# SSLidarboard.net
KiCad netlist of a schematic drawn in EAGLE
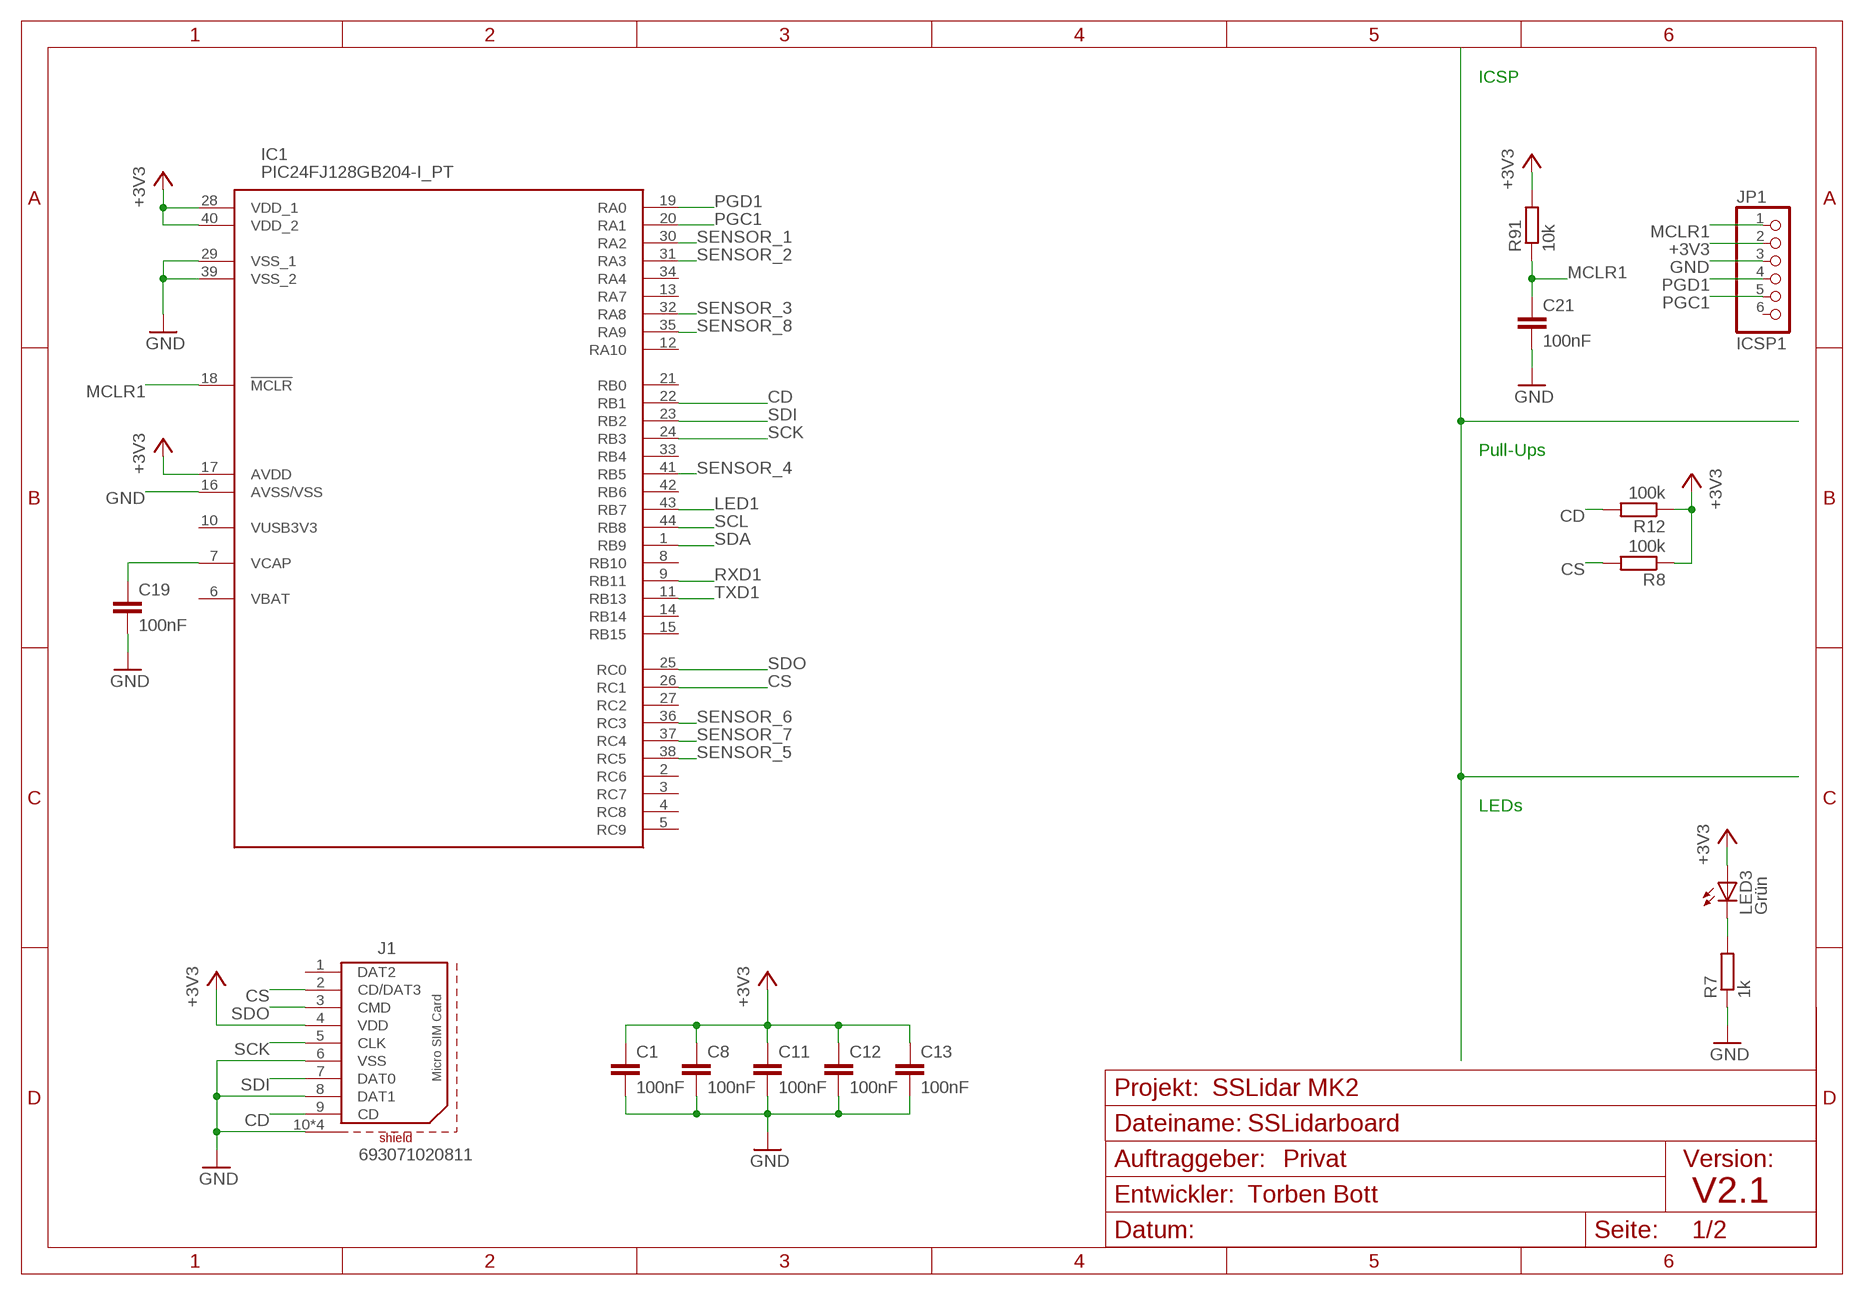
[diagram p0: schematic, sheet 1]
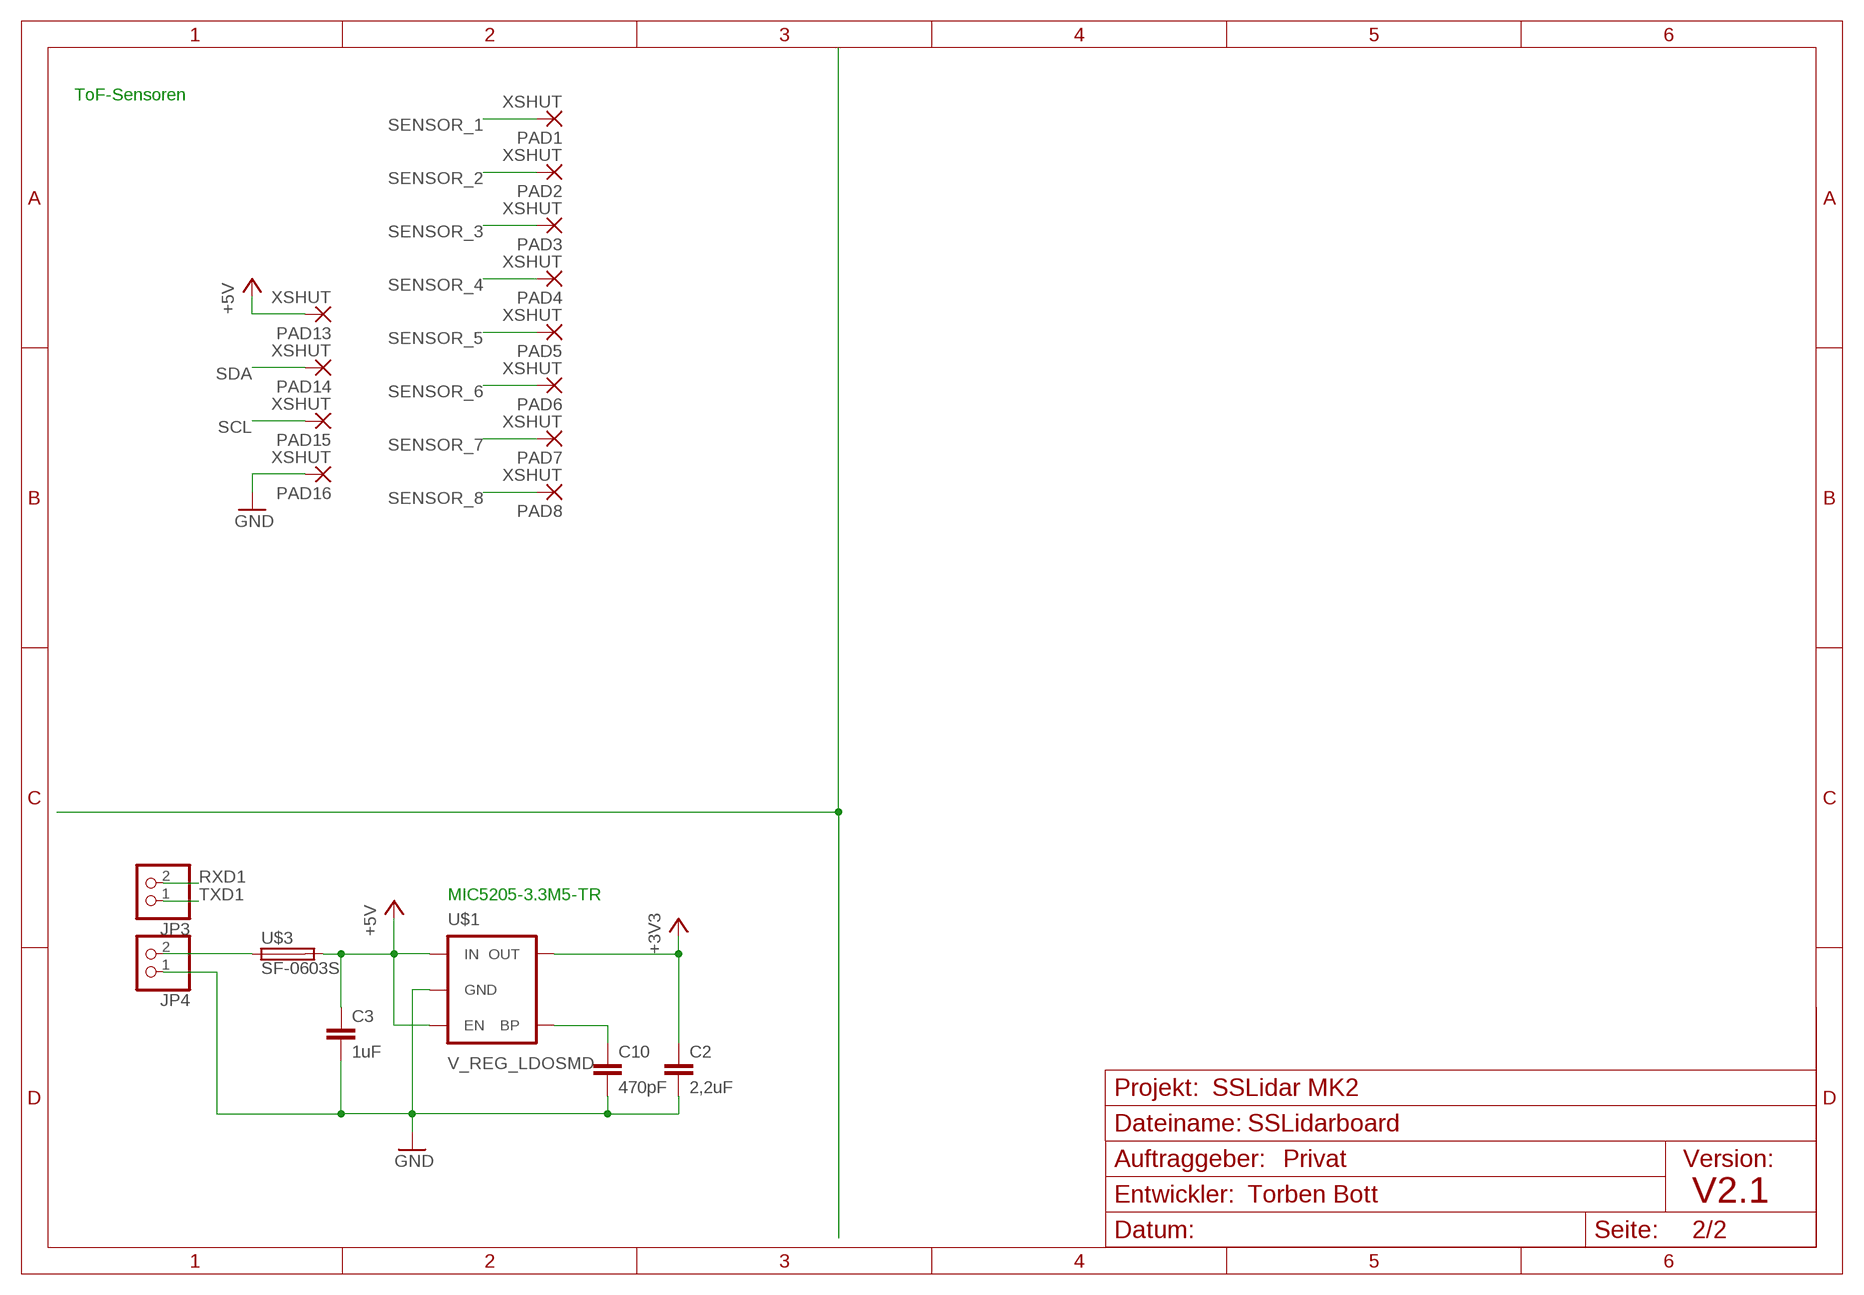
[diagram p1: schematic, sheet 2]

(export (version "E")
  (design (tool "Eeschema 10.0.6"))
  (components
    (comp (ref "C1")
      (value "100nF")
      (footprint "eagle-import:C0805")
      (libsource (lib "eagle-import") (part "C-EUC0805"))
    )
    (comp (ref "C8")
      (value "100nF")
      (footprint "eagle-import:C0805")
      (libsource (lib "eagle-import") (part "C-EUC0805"))
    )
    (comp (ref "C11")
      (value "100nF")
      (footprint "eagle-import:C0805")
      (libsource (lib "eagle-import") (part "C-EUC0805"))
    )
    (comp (ref "C12")
      (value "100nF")
      (footprint "eagle-import:C0805")
      (libsource (lib "eagle-import") (part "C-EUC0805"))
    )
    (comp (ref "C13")
      (value "100nF")
      (footprint "eagle-import:C0805")
      (libsource (lib "eagle-import") (part "C-EUC0805"))
    )
    (comp (ref "C19")
      (value "100nF")
      (footprint "eagle-import:C0805")
      (libsource (lib "eagle-import") (part "C-EUC0805"))
    )
    (comp (ref "C21")
      (value "100nF")
      (footprint "eagle-import:C0805")
      (libsource (lib "eagle-import") (part "C-EUC0805"))
    )
    (comp (ref "IC1")
      (value "PIC24FJ128GB204-I_PT")
      (footprint "eagle-import:QFP80P1200X1200X120-44N")
      (fields
        (field (name "MANUFACTURER_PART_NUMBER") "PIC24FJ128GB204-I/PT")
        (field (name "MOUSER_PART_NUMBER") "579-P24FJ128GB204IPT")
      )
      (libsource (lib "eagle-import") (part "PIC24FJ128GB204-I_PT"))
    )
    (comp (ref "J1")
      (value "693071020811")
      (footprint "eagle-import:693071020811")
      (libsource (lib "eagle-import") (part "693071020811"))
    )
    (comp (ref "JP1")
      (value "ICSP1")
      (footprint "eagle-import:1X06")
      (libsource (lib "eagle-import") (part "PINHD-1X6"))
    )
    (comp (ref "LED3")
      (value "Grün")
      (footprint "eagle-import:CHIPLED_0805")
      (libsource (lib "eagle-import") (part "LEDCHIPLED_0805"))
    )
    (comp (ref "R7")
      (value "1k")
      (footprint "eagle-import:R0805")
      (libsource (lib "eagle-import") (part "R-EU_R0805"))
    )
    (comp (ref "R8")
      (value "100k")
      (footprint "eagle-import:R0805")
      (libsource (lib "eagle-import") (part "R-EU_R0805"))
    )
    (comp (ref "R12")
      (value "100k")
      (footprint "eagle-import:R0805")
      (libsource (lib "eagle-import") (part "R-EU_R0805"))
    )
    (comp (ref "R91")
      (value "10k")
      (footprint "eagle-import:R0805")
      (libsource (lib "eagle-import") (part "R-EU_R0805"))
    )
    (comp (ref "C2")
      (value "2,2uF")
      (footprint "eagle-import:C0805")
      (libsource (lib "eagle-import") (part "C-EUC0805"))
    )
    (comp (ref "C3")
      (value "1uF")
      (footprint "eagle-import:C0805")
      (libsource (lib "eagle-import") (part "C-EUC0805"))
    )
    (comp (ref "C10")
      (value "470pF")
      (footprint "eagle-import:C0805")
      (libsource (lib "eagle-import") (part "C-EUC0805"))
    )
    (comp (ref "JP3")
      (value "PINHD-1X2")
      (footprint "eagle-import:1X02")
      (libsource (lib "eagle-import") (part "PINHD-1X2"))
    )
    (comp (ref "JP4")
      (value "PINHD-1X2")
      (footprint "eagle-import:1X02")
      (libsource (lib "eagle-import") (part "PINHD-1X2"))
    )
    (comp (ref "PAD1")
      (value "XSHUT")
      (footprint "eagle-import:SMD1,27-2,54")
      (libsource (lib "eagle-import") (part "WIREPADSMD1,27-254"))
    )
    (comp (ref "PAD2")
      (value "XSHUT")
      (footprint "eagle-import:SMD1,27-2,54")
      (libsource (lib "eagle-import") (part "WIREPADSMD1,27-254"))
    )
    (comp (ref "PAD3")
      (value "XSHUT")
      (footprint "eagle-import:SMD1,27-2,54")
      (libsource (lib "eagle-import") (part "WIREPADSMD1,27-254"))
    )
    (comp (ref "PAD4")
      (value "XSHUT")
      (footprint "eagle-import:SMD1,27-2,54")
      (libsource (lib "eagle-import") (part "WIREPADSMD1,27-254"))
    )
    (comp (ref "PAD5")
      (value "XSHUT")
      (footprint "eagle-import:SMD1,27-2,54")
      (libsource (lib "eagle-import") (part "WIREPADSMD1,27-254"))
    )
    (comp (ref "PAD6")
      (value "XSHUT")
      (footprint "eagle-import:SMD1,27-2,54")
      (libsource (lib "eagle-import") (part "WIREPADSMD1,27-254"))
    )
    (comp (ref "PAD7")
      (value "XSHUT")
      (footprint "eagle-import:SMD1,27-2,54")
      (libsource (lib "eagle-import") (part "WIREPADSMD1,27-254"))
    )
    (comp (ref "PAD8")
      (value "XSHUT")
      (footprint "eagle-import:SMD1,27-2,54")
      (libsource (lib "eagle-import") (part "WIREPADSMD1,27-254"))
    )
    (comp (ref "PAD13")
      (value "XSHUT")
      (footprint "eagle-import:SMD1,27-2,54")
      (libsource (lib "eagle-import") (part "WIREPADSMD1,27-254"))
    )
    (comp (ref "PAD14")
      (value "XSHUT")
      (footprint "eagle-import:SMD1,27-2,54")
      (libsource (lib "eagle-import") (part "WIREPADSMD1,27-254"))
    )
    (comp (ref "PAD15")
      (value "XSHUT")
      (footprint "eagle-import:SMD1,27-2,54")
      (libsource (lib "eagle-import") (part "WIREPADSMD1,27-254"))
    )
    (comp (ref "PAD16")
      (value "XSHUT")
      (footprint "eagle-import:SMD1,27-2,54")
      (libsource (lib "eagle-import") (part "WIREPADSMD1,27-254"))
    )
    (comp (ref "U$1")
      (value "V_REG_LDOSMD")
      (footprint "eagle-import:SOT23-5")
      (libsource (lib "eagle-import") (part "V_REG_LDOSMD"))
    )
    (comp (ref "U$3")
      (value "SF-0603S")
      (footprint "eagle-import:R0603")
      (libsource (lib "eagle-import") (part "SF-0603S"))
    )
  )
  (nets
    (net (code "1") (name "+3V3") (class "Default")
      (node (ref "C1") (pin "1") (pinfunction "1_1") (pintype "passive"))
      (node (ref "C11") (pin "1") (pinfunction "1_1") (pintype "passive"))
      (node (ref "C12") (pin "1") (pinfunction "1_1") (pintype "passive"))
      (node (ref "C13") (pin "1") (pinfunction "1_1") (pintype "passive"))
      (node (ref "C2") (pin "1") (pinfunction "1_1") (pintype "passive"))
      (node (ref "C8") (pin "1") (pinfunction "1_1") (pintype "passive"))
      (node (ref "IC1") (pin "17") (pinfunction "AVDD_17") (pintype "power_in"))
      (node (ref "IC1") (pin "28") (pinfunction "VDD_1_28") (pintype "power_in"))
      (node (ref "IC1") (pin "40") (pinfunction "VDD_2_40") (pintype "power_in"))
      (node (ref "J1") (pin "4") (pinfunction "VDD_4") (pintype "bidirectional"))
      (node (ref "JP1") (pin "2") (pinfunction "2_2") (pintype "passive"))
      (node (ref "LED3") (pin "A") (pinfunction "A_A") (pintype "passive"))
      (node (ref "R12") (pin "1") (pinfunction "1_1") (pintype "passive"))
      (node (ref "R8") (pin "1") (pinfunction "1_1") (pintype "passive"))
      (node (ref "R91") (pin "2") (pinfunction "2_2") (pintype "passive"))
      (node (ref "U$1") (pin "5") (pinfunction "OUT_5") (pintype "passive"))
    )
    (net (code "2") (name "+5V") (class "Default")
      (node (ref "C3") (pin "1") (pinfunction "1_1") (pintype "passive"))
      (node (ref "PAD13") (pin "1") (pinfunction "P_1") (pintype "passive"))
      (node (ref "U$1") (pin "1") (pinfunction "IN_1") (pintype "input"))
      (node (ref "U$1") (pin "3") (pinfunction "EN_3") (pintype "input"))
      (node (ref "U$3") (pin "2") (pinfunction "2_2") (pintype "passive"))
    )
    (net (code "3") (name "CD") (class "Default")
      (node (ref "IC1") (pin "22") (pinfunction "RB1_22") (pintype "bidirectional"))
      (node (ref "J1") (pin "9") (pinfunction "CD_9") (pintype "bidirectional"))
      (node (ref "R12") (pin "2") (pinfunction "2_2") (pintype "passive"))
    )
    (net (code "4") (name "CS") (class "Default")
      (node (ref "IC1") (pin "26") (pinfunction "RC1_26") (pintype "bidirectional"))
      (node (ref "J1") (pin "2") (pinfunction "CD/DAT3_2") (pintype "bidirectional"))
      (node (ref "R8") (pin "2") (pinfunction "2_2") (pintype "passive"))
    )
    (net (code "5") (name "GND") (class "Default")
      (node (ref "C1") (pin "2") (pinfunction "2_2") (pintype "passive"))
      (node (ref "C10") (pin "2") (pinfunction "2_2") (pintype "passive"))
      (node (ref "C11") (pin "2") (pinfunction "2_2") (pintype "passive"))
      (node (ref "C12") (pin "2") (pinfunction "2_2") (pintype "passive"))
      (node (ref "C13") (pin "2") (pinfunction "2_2") (pintype "passive"))
      (node (ref "C19") (pin "2") (pinfunction "2_2") (pintype "passive"))
      (node (ref "C2") (pin "2") (pinfunction "2_2") (pintype "passive"))
      (node (ref "C21") (pin "2") (pinfunction "2_2") (pintype "passive"))
      (node (ref "C3") (pin "2") (pinfunction "2_2") (pintype "passive"))
      (node (ref "C8") (pin "2") (pinfunction "2_2") (pintype "passive"))
      (node (ref "IC1") (pin "16") (pinfunction "AVSS/VSS_16") (pintype "power_in"))
      (node (ref "IC1") (pin "29") (pinfunction "VSS_1_29") (pintype "power_in"))
      (node (ref "IC1") (pin "39") (pinfunction "VSS_2_39") (pintype "power_in"))
      (node (ref "J1") (pin "10") (pinfunction "SHIELD_10") (pintype "bidirectional"))
      (node (ref "J1") (pin "11") (pinfunction "SHIELD_11") (pintype "bidirectional"))
      (node (ref "J1") (pin "12") (pinfunction "SHIELD_12") (pintype "bidirectional"))
      (node (ref "J1") (pin "13") (pinfunction "SHIELD_13") (pintype "bidirectional"))
      (node (ref "J1") (pin "6") (pinfunction "VSS_6") (pintype "bidirectional"))
      (node (ref "J1") (pin "8") (pinfunction "DAT1_8") (pintype "bidirectional"))
      (node (ref "JP1") (pin "3") (pinfunction "3_3") (pintype "passive"))
      (node (ref "JP4") (pin "1") (pinfunction "1_1") (pintype "passive"))
      (node (ref "PAD16") (pin "1") (pinfunction "P_1") (pintype "passive"))
      (node (ref "R7") (pin "1") (pinfunction "1_1") (pintype "passive"))
      (node (ref "U$1") (pin "2") (pinfunction "GND_2") (pintype "input"))
    )
    (net (code "6") (name "LED1") (class "Default")
      (node (ref "IC1") (pin "43") (pinfunction "RB7_43") (pintype "bidirectional"))
    )
    (net (code "7") (name "MCLR1") (class "Default")
      (node (ref "C21") (pin "1") (pinfunction "1_1") (pintype "passive"))
      (node (ref "IC1") (pin "18") (pinfunction "~{MCLR}_18") (pintype "bidirectional"))
      (node (ref "JP1") (pin "1") (pinfunction "1_1") (pintype "passive"))
      (node (ref "R91") (pin "1") (pinfunction "1_1") (pintype "passive"))
    )
    (net (code "8") (name "Net-(IC1-VCAP)") (class "Default")
      (node (ref "C19") (pin "1") (pinfunction "1_1") (pintype "passive"))
      (node (ref "IC1") (pin "7") (pinfunction "VCAP_7") (pintype "bidirectional"))
    )
    (net (code "9") (name "Net-(JP4-Pad2)") (class "Default")
      (node (ref "JP4") (pin "2") (pinfunction "2_2") (pintype "passive"))
      (node (ref "U$3") (pin "1") (pinfunction "1_1") (pintype "passive"))
    )
    (net (code "10") (name "Net-(LED3-PadC)") (class "Default")
      (node (ref "LED3") (pin "C") (pinfunction "C_C") (pintype "passive"))
      (node (ref "R7") (pin "2") (pinfunction "2_2") (pintype "passive"))
    )
    (net (code "11") (name "Net-(U$1-BP)") (class "Default")
      (node (ref "C10") (pin "1") (pinfunction "1_1") (pintype "passive"))
      (node (ref "U$1") (pin "4") (pinfunction "BP_4") (pintype "input"))
    )
    (net (code "12") (name "PGC1") (class "Default")
      (node (ref "IC1") (pin "20") (pinfunction "RA1_20") (pintype "bidirectional"))
      (node (ref "JP1") (pin "5") (pinfunction "5_5") (pintype "passive"))
    )
    (net (code "13") (name "PGD1") (class "Default")
      (node (ref "IC1") (pin "19") (pinfunction "RA0_19") (pintype "bidirectional"))
      (node (ref "JP1") (pin "4") (pinfunction "4_4") (pintype "passive"))
    )
    (net (code "14") (name "RXD1") (class "Default")
      (node (ref "IC1") (pin "9") (pinfunction "RB11_9") (pintype "bidirectional"))
      (node (ref "JP3") (pin "2") (pinfunction "2_2") (pintype "passive"))
    )
    (net (code "15") (name "SCK") (class "Default")
      (node (ref "IC1") (pin "24") (pinfunction "RB3_24") (pintype "bidirectional"))
      (node (ref "J1") (pin "5") (pinfunction "CLK_5") (pintype "bidirectional"))
    )
    (net (code "16") (name "SCL") (class "Default")
      (node (ref "IC1") (pin "44") (pinfunction "RB8_44") (pintype "bidirectional"))
      (node (ref "PAD15") (pin "1") (pinfunction "P_1") (pintype "passive"))
    )
    (net (code "17") (name "SDA") (class "Default")
      (node (ref "IC1") (pin "1") (pinfunction "RB9_1") (pintype "bidirectional"))
      (node (ref "PAD14") (pin "1") (pinfunction "P_1") (pintype "passive"))
    )
    (net (code "18") (name "SDI") (class "Default")
      (node (ref "IC1") (pin "23") (pinfunction "RB2_23") (pintype "bidirectional"))
      (node (ref "J1") (pin "7") (pinfunction "DAT0_7") (pintype "bidirectional"))
    )
    (net (code "19") (name "SDO") (class "Default")
      (node (ref "IC1") (pin "25") (pinfunction "RC0_25") (pintype "bidirectional"))
      (node (ref "J1") (pin "3") (pinfunction "CMD_3") (pintype "bidirectional"))
    )
    (net (code "20") (name "SENSOR_1") (class "Default")
      (node (ref "IC1") (pin "30") (pinfunction "RA2_30") (pintype "bidirectional"))
      (node (ref "PAD1") (pin "1") (pinfunction "P_1") (pintype "passive"))
    )
    (net (code "21") (name "SENSOR_2") (class "Default")
      (node (ref "IC1") (pin "31") (pinfunction "RA3_31") (pintype "bidirectional"))
      (node (ref "PAD2") (pin "1") (pinfunction "P_1") (pintype "passive"))
    )
    (net (code "22") (name "SENSOR_3") (class "Default")
      (node (ref "IC1") (pin "32") (pinfunction "RA8_32") (pintype "bidirectional"))
      (node (ref "PAD3") (pin "1") (pinfunction "P_1") (pintype "passive"))
    )
    (net (code "23") (name "SENSOR_4") (class "Default")
      (node (ref "IC1") (pin "41") (pinfunction "RB5_41") (pintype "bidirectional"))
      (node (ref "PAD4") (pin "1") (pinfunction "P_1") (pintype "passive"))
    )
    (net (code "24") (name "SENSOR_5") (class "Default")
      (node (ref "IC1") (pin "38") (pinfunction "RC5_38") (pintype "bidirectional"))
      (node (ref "PAD5") (pin "1") (pinfunction "P_1") (pintype "passive"))
    )
    (net (code "25") (name "SENSOR_6") (class "Default")
      (node (ref "IC1") (pin "36") (pinfunction "RC3_36") (pintype "bidirectional"))
      (node (ref "PAD6") (pin "1") (pinfunction "P_1") (pintype "passive"))
    )
    (net (code "26") (name "SENSOR_7") (class "Default")
      (node (ref "IC1") (pin "37") (pinfunction "RC4_37") (pintype "bidirectional"))
      (node (ref "PAD7") (pin "1") (pinfunction "P_1") (pintype "passive"))
    )
    (net (code "27") (name "SENSOR_8") (class "Default")
      (node (ref "IC1") (pin "35") (pinfunction "RA9_35") (pintype "bidirectional"))
      (node (ref "PAD8") (pin "1") (pinfunction "P_1") (pintype "passive"))
    )
    (net (code "28") (name "TXD1") (class "Default")
      (node (ref "IC1") (pin "11") (pinfunction "RB13_11") (pintype "bidirectional"))
      (node (ref "JP3") (pin "1") (pinfunction "1_1") (pintype "passive"))
    )
    (net (code "29") (name "unconnected-(IC1-RA4-Pad34)") (class "Default")
      (node (ref "IC1") (pin "34") (pinfunction "RA4_34") (pintype "bidirectional"))
    )
    (net (code "30") (name "unconnected-(IC1-RA7-Pad13)") (class "Default")
      (node (ref "IC1") (pin "13") (pinfunction "RA7_13") (pintype "bidirectional"))
    )
    (net (code "31") (name "unconnected-(IC1-RA10-Pad12)") (class "Default")
      (node (ref "IC1") (pin "12") (pinfunction "RA10_12") (pintype "bidirectional"))
    )
    (net (code "32") (name "unconnected-(IC1-RB0-Pad21)") (class "Default")
      (node (ref "IC1") (pin "21") (pinfunction "RB0_21") (pintype "bidirectional"))
    )
    (net (code "33") (name "unconnected-(IC1-RB4-Pad33)") (class "Default")
      (node (ref "IC1") (pin "33") (pinfunction "RB4_33") (pintype "bidirectional"))
    )
    (net (code "34") (name "unconnected-(IC1-RB6-Pad42)") (class "Default")
      (node (ref "IC1") (pin "42") (pinfunction "RB6_42") (pintype "bidirectional"))
    )
    (net (code "35") (name "unconnected-(IC1-RB10-Pad8)") (class "Default")
      (node (ref "IC1") (pin "8") (pinfunction "RB10_8") (pintype "bidirectional"))
    )
    (net (code "36") (name "unconnected-(IC1-RB14-Pad14)") (class "Default")
      (node (ref "IC1") (pin "14") (pinfunction "RB14_14") (pintype "bidirectional"))
    )
    (net (code "37") (name "unconnected-(IC1-RB15-Pad15)") (class "Default")
      (node (ref "IC1") (pin "15") (pinfunction "RB15_15") (pintype "bidirectional"))
    )
    (net (code "38") (name "unconnected-(IC1-RC2-Pad27)") (class "Default")
      (node (ref "IC1") (pin "27") (pinfunction "RC2_27") (pintype "bidirectional"))
    )
    (net (code "39") (name "unconnected-(IC1-RC6-Pad2)") (class "Default")
      (node (ref "IC1") (pin "2") (pinfunction "RC6_2") (pintype "bidirectional"))
    )
    (net (code "40") (name "unconnected-(IC1-RC7-Pad3)") (class "Default")
      (node (ref "IC1") (pin "3") (pinfunction "RC7_3") (pintype "bidirectional"))
    )
    (net (code "41") (name "unconnected-(IC1-RC8-Pad4)") (class "Default")
      (node (ref "IC1") (pin "4") (pinfunction "RC8_4") (pintype "bidirectional"))
    )
    (net (code "42") (name "unconnected-(IC1-RC9-Pad5)") (class "Default")
      (node (ref "IC1") (pin "5") (pinfunction "RC9_5") (pintype "bidirectional"))
    )
    (net (code "43") (name "unconnected-(IC1-VBAT-Pad6)") (class "Default")
      (node (ref "IC1") (pin "6") (pinfunction "VBAT_6") (pintype "bidirectional"))
    )
    (net (code "44") (name "unconnected-(IC1-VUSB3V3-Pad10)") (class "Default")
      (node (ref "IC1") (pin "10") (pinfunction "VUSB3V3_10") (pintype "bidirectional"))
    )
    (net (code "45") (name "unconnected-(J1-DAT2-Pad1)") (class "Default")
      (node (ref "J1") (pin "1") (pinfunction "DAT2_1") (pintype "bidirectional"))
    )
    (net (code "46") (name "unconnected-(JP1-Pad6)") (class "Default")
      (node (ref "JP1") (pin "6") (pinfunction "6_6") (pintype "passive"))
    )
  )
)
